# design.net
KiCad netlist of a schematic drawn in Altium Designer
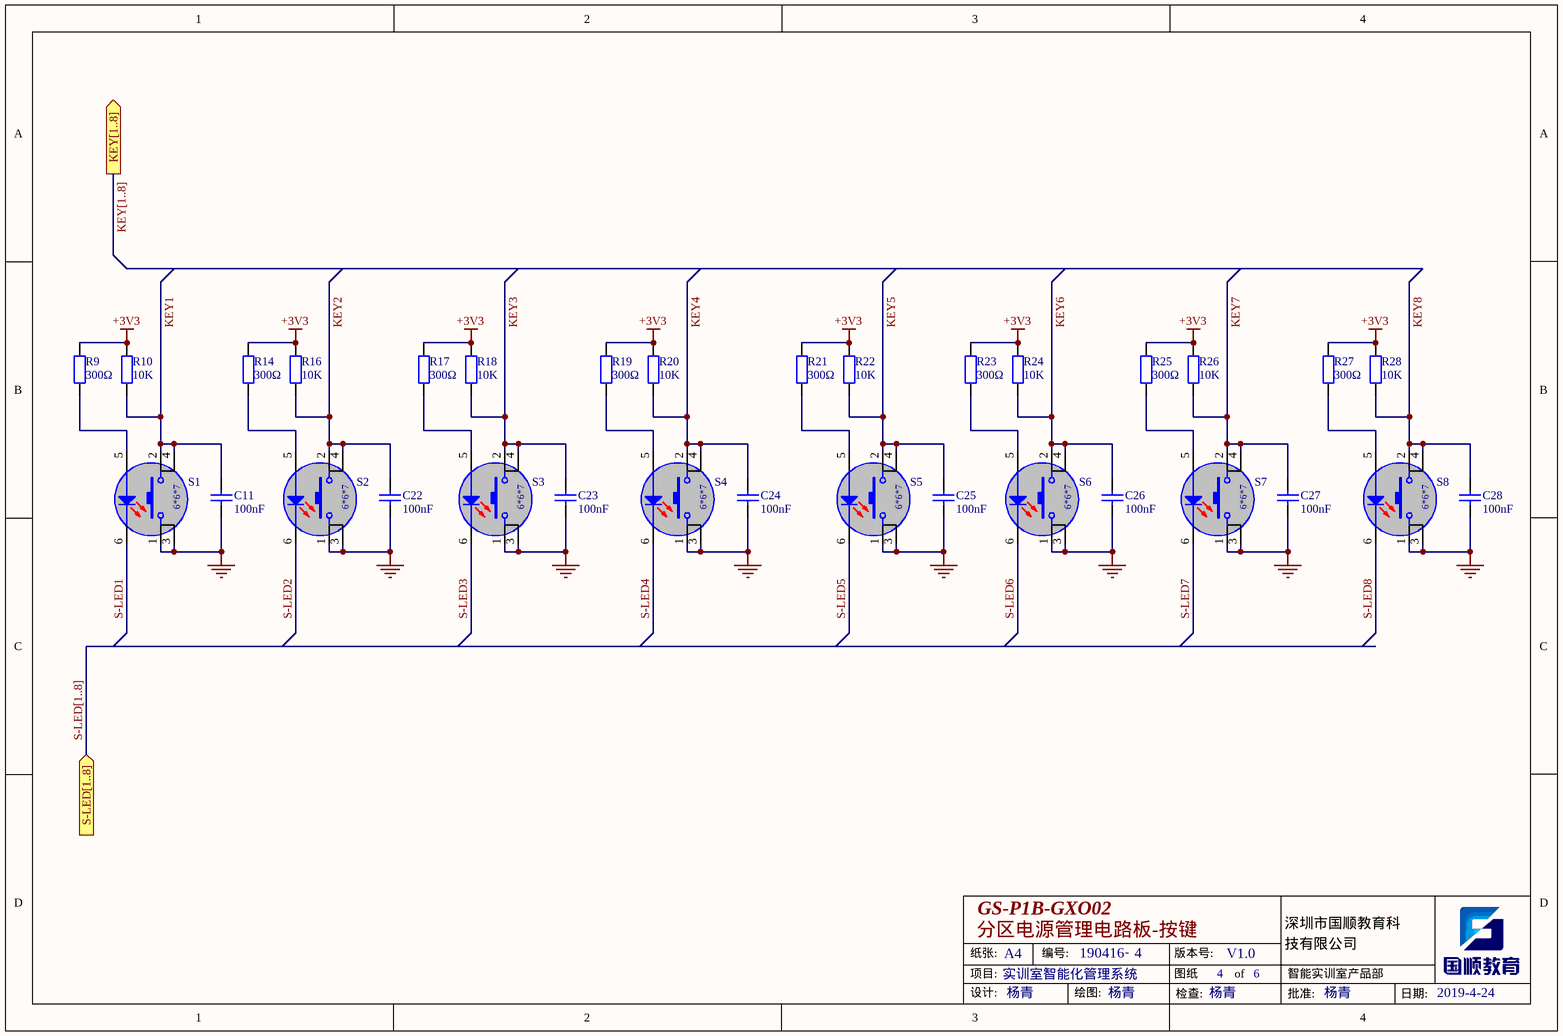
[diagram p0: 按键.SchDoc]

(export (version "E")
  (design (tool "Eeschema 10.0.6"))
  (components
    (comp (ref "C11")
      (value "100nF")
      (footprint "C0603")
      (description "Capacitor")
      (libsource (lib "贴片电容") (part "100nF_50V_0603"))
    )
    (comp (ref "C22")
      (value "100nF")
      (footprint "C0603")
      (description "Capacitor")
      (libsource (lib "贴片电容") (part "100nF_50V_0603"))
    )
    (comp (ref "C23")
      (value "100nF")
      (footprint "C0603")
      (description "Capacitor")
      (libsource (lib "贴片电容") (part "100nF_50V_0603"))
    )
    (comp (ref "C24")
      (value "100nF")
      (footprint "C0603")
      (description "Capacitor")
      (libsource (lib "贴片电容") (part "100nF_50V_0603"))
    )
    (comp (ref "C25")
      (value "100nF")
      (footprint "C0603")
      (description "Capacitor")
      (libsource (lib "贴片电容") (part "100nF_50V_0603"))
    )
    (comp (ref "C26")
      (value "100nF")
      (footprint "C0603")
      (description "Capacitor")
      (libsource (lib "贴片电容") (part "100nF_50V_0603"))
    )
    (comp (ref "C27")
      (value "100nF")
      (footprint "C0603")
      (description "Capacitor")
      (libsource (lib "贴片电容") (part "100nF_50V_0603"))
    )
    (comp (ref "C28")
      (value "100nF")
      (footprint "C0603")
      (description "Capacitor")
      (libsource (lib "贴片电容") (part "100nF_50V_0603"))
    )
    (comp (ref "R9")
      (value "300Ω")
      (footprint "R0603")
      (description "300Ω,±5%,0603")
      (libsource (lib "贴片电阻") (part "300Ω_5%_0603"))
    )
    (comp (ref "R10")
      (value "10K")
      (footprint "R0603")
      (description "10K,±5%,0603")
      (libsource (lib "贴片电阻") (part "10K_5%_0603"))
    )
    (comp (ref "R14")
      (value "300Ω")
      (footprint "R0603")
      (description "300Ω,±5%,0603")
      (libsource (lib "贴片电阻") (part "300Ω_5%_0603"))
    )
    (comp (ref "R16")
      (value "10K")
      (footprint "R0603")
      (description "10K,±5%,0603")
      (libsource (lib "贴片电阻") (part "10K_5%_0603"))
    )
    (comp (ref "R17")
      (value "300Ω")
      (footprint "R0603")
      (description "300Ω,±5%,0603")
      (libsource (lib "贴片电阻") (part "300Ω_5%_0603"))
    )
    (comp (ref "R18")
      (value "10K")
      (footprint "R0603")
      (description "10K,±5%,0603")
      (libsource (lib "贴片电阻") (part "10K_5%_0603"))
    )
    (comp (ref "R19")
      (value "300Ω")
      (footprint "R0603")
      (description "300Ω,±5%,0603")
      (libsource (lib "贴片电阻") (part "300Ω_5%_0603"))
    )
    (comp (ref "R20")
      (value "10K")
      (footprint "R0603")
      (description "10K,±5%,0603")
      (libsource (lib "贴片电阻") (part "10K_5%_0603"))
    )
    (comp (ref "R21")
      (value "300Ω")
      (footprint "R0603")
      (description "300Ω,±5%,0603")
      (libsource (lib "贴片电阻") (part "300Ω_5%_0603"))
    )
    (comp (ref "R22")
      (value "10K")
      (footprint "R0603")
      (description "10K,±5%,0603")
      (libsource (lib "贴片电阻") (part "10K_5%_0603"))
    )
    (comp (ref "R23")
      (value "300Ω")
      (footprint "R0603")
      (description "300Ω,±5%,0603")
      (libsource (lib "贴片电阻") (part "300Ω_5%_0603"))
    )
    (comp (ref "R24")
      (value "10K")
      (footprint "R0603")
      (description "10K,±5%,0603")
      (libsource (lib "贴片电阻") (part "10K_5%_0603"))
    )
    (comp (ref "R25")
      (value "300Ω")
      (footprint "R0603")
      (description "300Ω,±5%,0603")
      (libsource (lib "贴片电阻") (part "300Ω_5%_0603"))
    )
    (comp (ref "R26")
      (value "10K")
      (footprint "R0603")
      (description "10K,±5%,0603")
      (libsource (lib "贴片电阻") (part "10K_5%_0603"))
    )
    (comp (ref "R27")
      (value "300Ω")
      (footprint "R0603")
      (description "300Ω,±5%,0603")
      (libsource (lib "贴片电阻") (part "300Ω_5%_0603"))
    )
    (comp (ref "R28")
      (value "10K")
      (footprint "R0603")
      (description "10K,±5%,0603")
      (libsource (lib "贴片电阻") (part "10K_5%_0603"))
    )
    (comp (ref "S1")
      (value "6X6X7")
      (footprint "SW2-6X6X7-Lamp")
      (description "6X6X7,带灯,6PIN")
      (libsource (lib "按键开关") (part "SW-PB_6X6X7-6P-LAMP"))
    )
    (comp (ref "S2")
      (value "6X6X7")
      (footprint "SW2-6X6X7-Lamp")
      (description "6X6X7,带灯,6PIN")
      (libsource (lib "按键开关") (part "SW-PB_6X6X7-6P-LAMP"))
    )
    (comp (ref "S3")
      (value "6X6X7")
      (footprint "SW2-6X6X7-Lamp")
      (description "6X6X7,带灯,6PIN")
      (libsource (lib "按键开关") (part "SW-PB_6X6X7-6P-LAMP"))
    )
    (comp (ref "S4")
      (value "6X6X7")
      (footprint "SW2-6X6X7-Lamp")
      (description "6X6X7,带灯,6PIN")
      (libsource (lib "按键开关") (part "SW-PB_6X6X7-6P-LAMP"))
    )
    (comp (ref "S5")
      (value "6X6X7")
      (footprint "SW2-6X6X7-Lamp")
      (description "6X6X7,带灯,6PIN")
      (libsource (lib "按键开关") (part "SW-PB_6X6X7-6P-LAMP"))
    )
    (comp (ref "S6")
      (value "6X6X7")
      (footprint "SW2-6X6X7-Lamp")
      (description "6X6X7,带灯,6PIN")
      (libsource (lib "按键开关") (part "SW-PB_6X6X7-6P-LAMP"))
    )
    (comp (ref "S7")
      (value "6X6X7")
      (footprint "SW2-6X6X7-Lamp")
      (description "6X6X7,带灯,6PIN")
      (libsource (lib "按键开关") (part "SW-PB_6X6X7-6P-LAMP"))
    )
    (comp (ref "S8")
      (value "6X6X7")
      (footprint "SW2-6X6X7-Lamp")
      (description "6X6X7,带灯,6PIN")
      (libsource (lib "按键开关") (part "SW-PB_6X6X7-6P-LAMP"))
    )
  )
  (nets
    (net (code "1") (name "+3V3") (class "Default")
      (node (ref "R10") (pin "1") (pinfunction "1_1") (pintype "passive"))
      (node (ref "R14") (pin "1") (pinfunction "1_1") (pintype "passive"))
      (node (ref "R16") (pin "1") (pinfunction "1_1") (pintype "passive"))
      (node (ref "R17") (pin "1") (pinfunction "1_1") (pintype "passive"))
      (node (ref "R18") (pin "1") (pinfunction "1_1") (pintype "passive"))
      (node (ref "R19") (pin "1") (pinfunction "1_1") (pintype "passive"))
      (node (ref "R20") (pin "1") (pinfunction "1_1") (pintype "passive"))
      (node (ref "R21") (pin "1") (pinfunction "1_1") (pintype "passive"))
      (node (ref "R22") (pin "1") (pinfunction "1_1") (pintype "passive"))
      (node (ref "R23") (pin "1") (pinfunction "1_1") (pintype "passive"))
      (node (ref "R24") (pin "1") (pinfunction "1_1") (pintype "passive"))
      (node (ref "R25") (pin "1") (pinfunction "1_1") (pintype "passive"))
      (node (ref "R26") (pin "1") (pinfunction "1_1") (pintype "passive"))
      (node (ref "R27") (pin "1") (pinfunction "1_1") (pintype "passive"))
      (node (ref "R28") (pin "1") (pinfunction "1_1") (pintype "passive"))
      (node (ref "R9") (pin "1") (pinfunction "1_1") (pintype "passive"))
    )
    (net (code "2") (name "/KEY1") (class "Default")
      (node (ref "C11") (pin "2") (pinfunction "2_2") (pintype "passive"))
      (node (ref "R10") (pin "2") (pinfunction "2_2") (pintype "passive"))
      (node (ref "S1") (pin "2") (pinfunction "2_2") (pintype "passive"))
      (node (ref "S1") (pin "4") (pinfunction "4_4") (pintype "passive"))
    )
    (net (code "3") (name "/KEY2") (class "Default")
      (node (ref "C22") (pin "2") (pinfunction "2_2") (pintype "passive"))
      (node (ref "R16") (pin "2") (pinfunction "2_2") (pintype "passive"))
      (node (ref "S2") (pin "2") (pinfunction "2_2") (pintype "passive"))
      (node (ref "S2") (pin "4") (pinfunction "4_4") (pintype "passive"))
    )
    (net (code "4") (name "/KEY3") (class "Default")
      (node (ref "C23") (pin "2") (pinfunction "2_2") (pintype "passive"))
      (node (ref "R18") (pin "2") (pinfunction "2_2") (pintype "passive"))
      (node (ref "S3") (pin "2") (pinfunction "2_2") (pintype "passive"))
      (node (ref "S3") (pin "4") (pinfunction "4_4") (pintype "passive"))
    )
    (net (code "5") (name "/KEY4") (class "Default")
      (node (ref "C24") (pin "2") (pinfunction "2_2") (pintype "passive"))
      (node (ref "R20") (pin "2") (pinfunction "2_2") (pintype "passive"))
      (node (ref "S4") (pin "2") (pinfunction "2_2") (pintype "passive"))
      (node (ref "S4") (pin "4") (pinfunction "4_4") (pintype "passive"))
    )
    (net (code "6") (name "/KEY5") (class "Default")
      (node (ref "C25") (pin "2") (pinfunction "2_2") (pintype "passive"))
      (node (ref "R22") (pin "2") (pinfunction "2_2") (pintype "passive"))
      (node (ref "S5") (pin "2") (pinfunction "2_2") (pintype "passive"))
      (node (ref "S5") (pin "4") (pinfunction "4_4") (pintype "passive"))
    )
    (net (code "7") (name "/KEY6") (class "Default")
      (node (ref "C26") (pin "2") (pinfunction "2_2") (pintype "passive"))
      (node (ref "R24") (pin "2") (pinfunction "2_2") (pintype "passive"))
      (node (ref "S6") (pin "2") (pinfunction "2_2") (pintype "passive"))
      (node (ref "S6") (pin "4") (pinfunction "4_4") (pintype "passive"))
    )
    (net (code "8") (name "/KEY7") (class "Default")
      (node (ref "C27") (pin "2") (pinfunction "2_2") (pintype "passive"))
      (node (ref "R26") (pin "2") (pinfunction "2_2") (pintype "passive"))
      (node (ref "S7") (pin "2") (pinfunction "2_2") (pintype "passive"))
      (node (ref "S7") (pin "4") (pinfunction "4_4") (pintype "passive"))
    )
    (net (code "9") (name "/KEY8") (class "Default")
      (node (ref "C28") (pin "2") (pinfunction "2_2") (pintype "passive"))
      (node (ref "R28") (pin "2") (pinfunction "2_2") (pintype "passive"))
      (node (ref "S8") (pin "2") (pinfunction "2_2") (pintype "passive"))
      (node (ref "S8") (pin "4") (pinfunction "4_4") (pintype "passive"))
    )
    (net (code "11") (name "/S-LED1") (class "Default")
      (node (ref "S1") (pin "6") (pinfunction "6_6") (pintype "passive"))
    )
    (net (code "12") (name "/S-LED2") (class "Default")
      (node (ref "S2") (pin "6") (pinfunction "6_6") (pintype "passive"))
    )
    (net (code "13") (name "/S-LED3") (class "Default")
      (node (ref "S3") (pin "6") (pinfunction "6_6") (pintype "passive"))
    )
    (net (code "14") (name "/S-LED4") (class "Default")
      (node (ref "S4") (pin "6") (pinfunction "6_6") (pintype "passive"))
    )
    (net (code "15") (name "/S-LED5") (class "Default")
      (node (ref "S5") (pin "6") (pinfunction "6_6") (pintype "passive"))
    )
    (net (code "16") (name "/S-LED6") (class "Default")
      (node (ref "S6") (pin "6") (pinfunction "6_6") (pintype "passive"))
    )
    (net (code "17") (name "/S-LED7") (class "Default")
      (node (ref "S7") (pin "6") (pinfunction "6_6") (pintype "passive"))
    )
    (net (code "18") (name "/S-LED8") (class "Default")
      (node (ref "S8") (pin "6") (pinfunction "6_6") (pintype "passive"))
    )
    (net (code "20") (name "GND") (class "Default")
      (node (ref "C11") (pin "1") (pinfunction "1_1") (pintype "passive"))
      (node (ref "C22") (pin "1") (pinfunction "1_1") (pintype "passive"))
      (node (ref "C23") (pin "1") (pinfunction "1_1") (pintype "passive"))
      (node (ref "C24") (pin "1") (pinfunction "1_1") (pintype "passive"))
      (node (ref "C25") (pin "1") (pinfunction "1_1") (pintype "passive"))
      (node (ref "C26") (pin "1") (pinfunction "1_1") (pintype "passive"))
      (node (ref "C27") (pin "1") (pinfunction "1_1") (pintype "passive"))
      (node (ref "C28") (pin "1") (pinfunction "1_1") (pintype "passive"))
      (node (ref "S1") (pin "1") (pinfunction "1_1") (pintype "passive"))
      (node (ref "S1") (pin "3") (pinfunction "3_3") (pintype "passive"))
      (node (ref "S2") (pin "1") (pinfunction "1_1") (pintype "passive"))
      (node (ref "S2") (pin "3") (pinfunction "3_3") (pintype "passive"))
      (node (ref "S3") (pin "1") (pinfunction "1_1") (pintype "passive"))
      (node (ref "S3") (pin "3") (pinfunction "3_3") (pintype "passive"))
      (node (ref "S4") (pin "1") (pinfunction "1_1") (pintype "passive"))
      (node (ref "S4") (pin "3") (pinfunction "3_3") (pintype "passive"))
      (node (ref "S5") (pin "1") (pinfunction "1_1") (pintype "passive"))
      (node (ref "S5") (pin "3") (pinfunction "3_3") (pintype "passive"))
      (node (ref "S6") (pin "1") (pinfunction "1_1") (pintype "passive"))
      (node (ref "S6") (pin "3") (pinfunction "3_3") (pintype "passive"))
      (node (ref "S7") (pin "1") (pinfunction "1_1") (pintype "passive"))
      (node (ref "S7") (pin "3") (pinfunction "3_3") (pintype "passive"))
      (node (ref "S8") (pin "1") (pinfunction "1_1") (pintype "passive"))
      (node (ref "S8") (pin "3") (pinfunction "3_3") (pintype "passive"))
    )
    (net (code "21") (name "Net-(R9-Pad2)") (class "Default")
      (node (ref "R9") (pin "2") (pinfunction "2_2") (pintype "passive"))
      (node (ref "S1") (pin "5") (pinfunction "5_5") (pintype "passive"))
    )
    (net (code "22") (name "Net-(R14-Pad2)") (class "Default")
      (node (ref "R14") (pin "2") (pinfunction "2_2") (pintype "passive"))
      (node (ref "S2") (pin "5") (pinfunction "5_5") (pintype "passive"))
    )
    (net (code "23") (name "Net-(R17-Pad2)") (class "Default")
      (node (ref "R17") (pin "2") (pinfunction "2_2") (pintype "passive"))
      (node (ref "S3") (pin "5") (pinfunction "5_5") (pintype "passive"))
    )
    (net (code "24") (name "Net-(R19-Pad2)") (class "Default")
      (node (ref "R19") (pin "2") (pinfunction "2_2") (pintype "passive"))
      (node (ref "S4") (pin "5") (pinfunction "5_5") (pintype "passive"))
    )
    (net (code "25") (name "Net-(R21-Pad2)") (class "Default")
      (node (ref "R21") (pin "2") (pinfunction "2_2") (pintype "passive"))
      (node (ref "S5") (pin "5") (pinfunction "5_5") (pintype "passive"))
    )
    (net (code "26") (name "Net-(R23-Pad2)") (class "Default")
      (node (ref "R23") (pin "2") (pinfunction "2_2") (pintype "passive"))
      (node (ref "S6") (pin "5") (pinfunction "5_5") (pintype "passive"))
    )
    (net (code "27") (name "Net-(R25-Pad2)") (class "Default")
      (node (ref "R25") (pin "2") (pinfunction "2_2") (pintype "passive"))
      (node (ref "S7") (pin "5") (pinfunction "5_5") (pintype "passive"))
    )
    (net (code "28") (name "Net-(R27-Pad2)") (class "Default")
      (node (ref "R27") (pin "2") (pinfunction "2_2") (pintype "passive"))
      (node (ref "S8") (pin "5") (pinfunction "5_5") (pintype "passive"))
    )
  )
)
